# vca.net
KiCad netlist of a schematic drawn in EAGLE
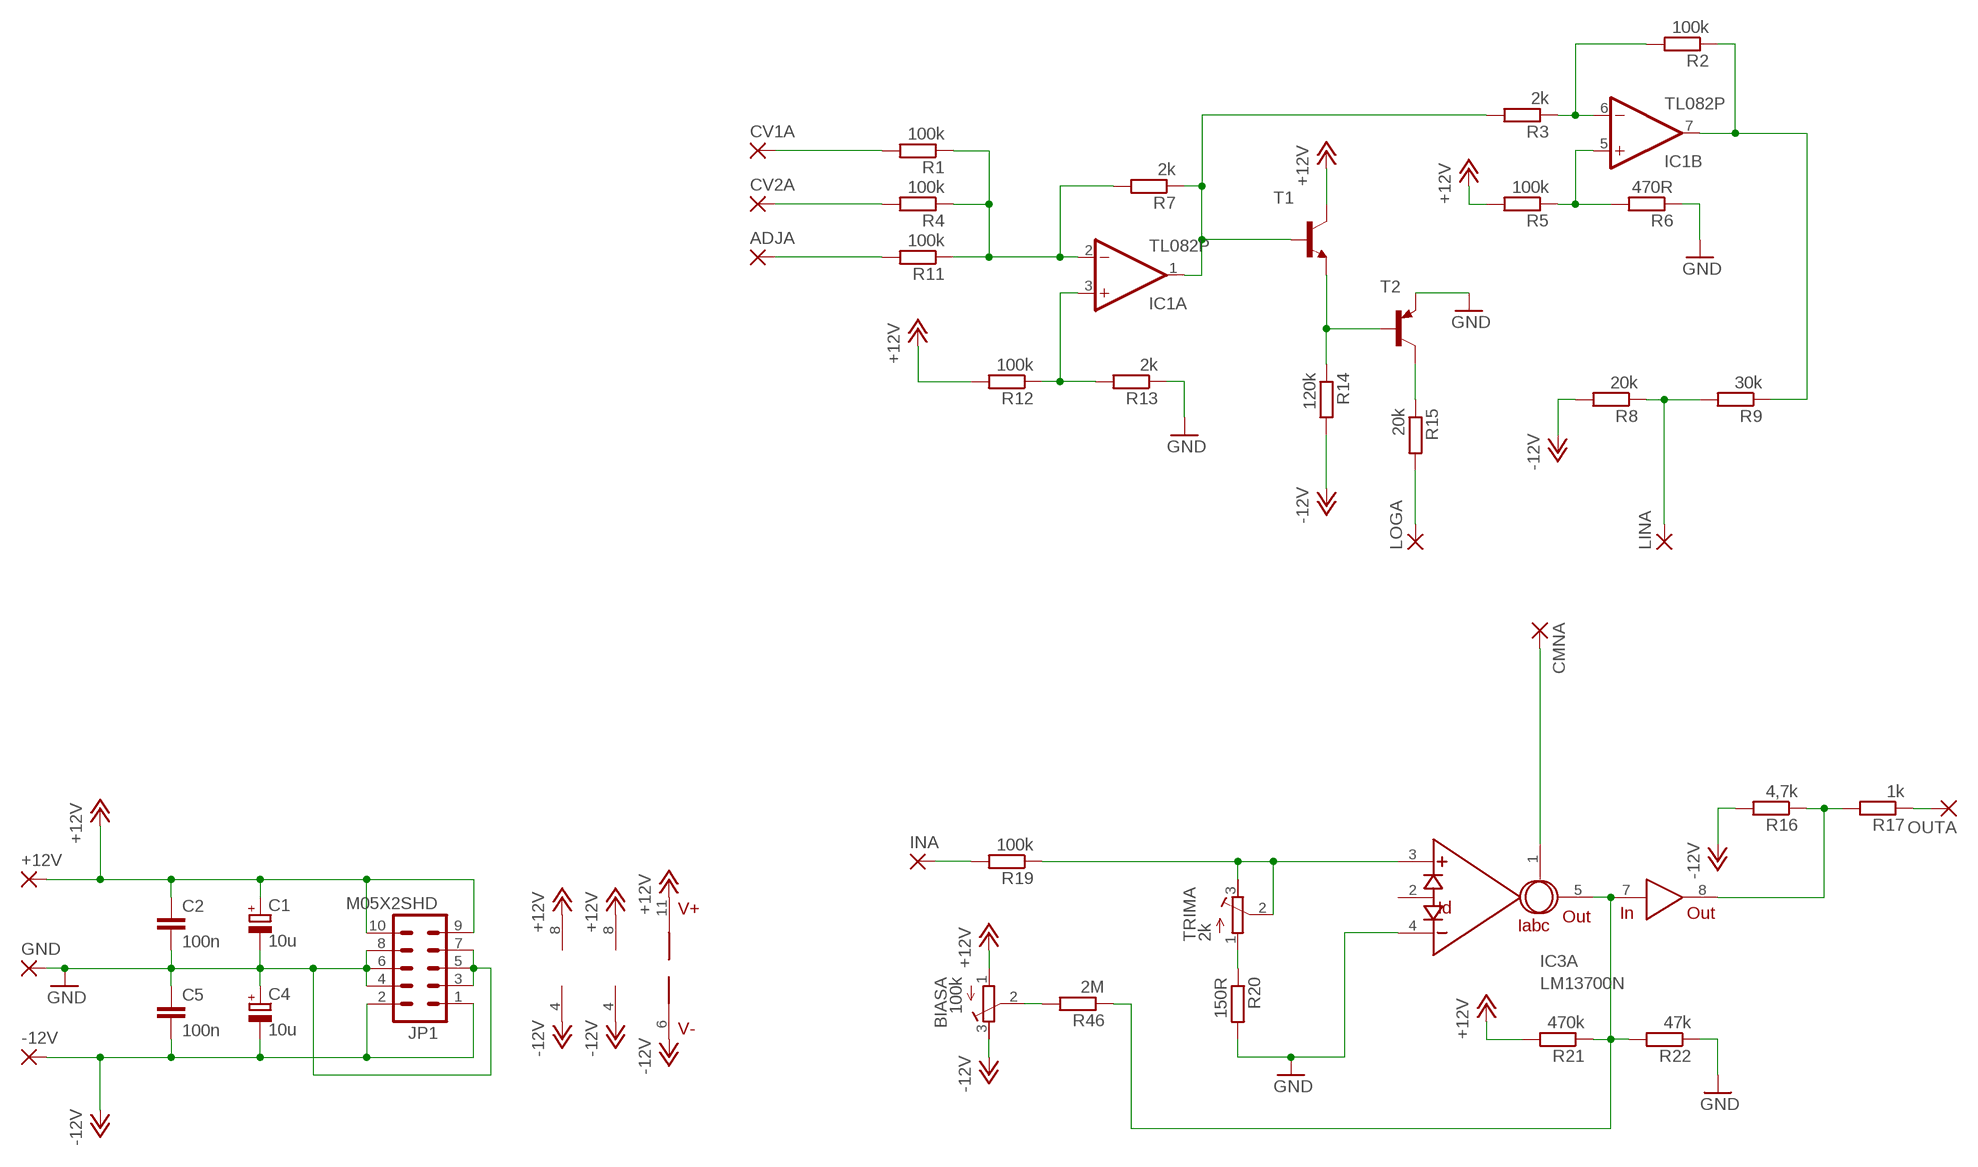
[diagram p0: schematic, sheet 1]
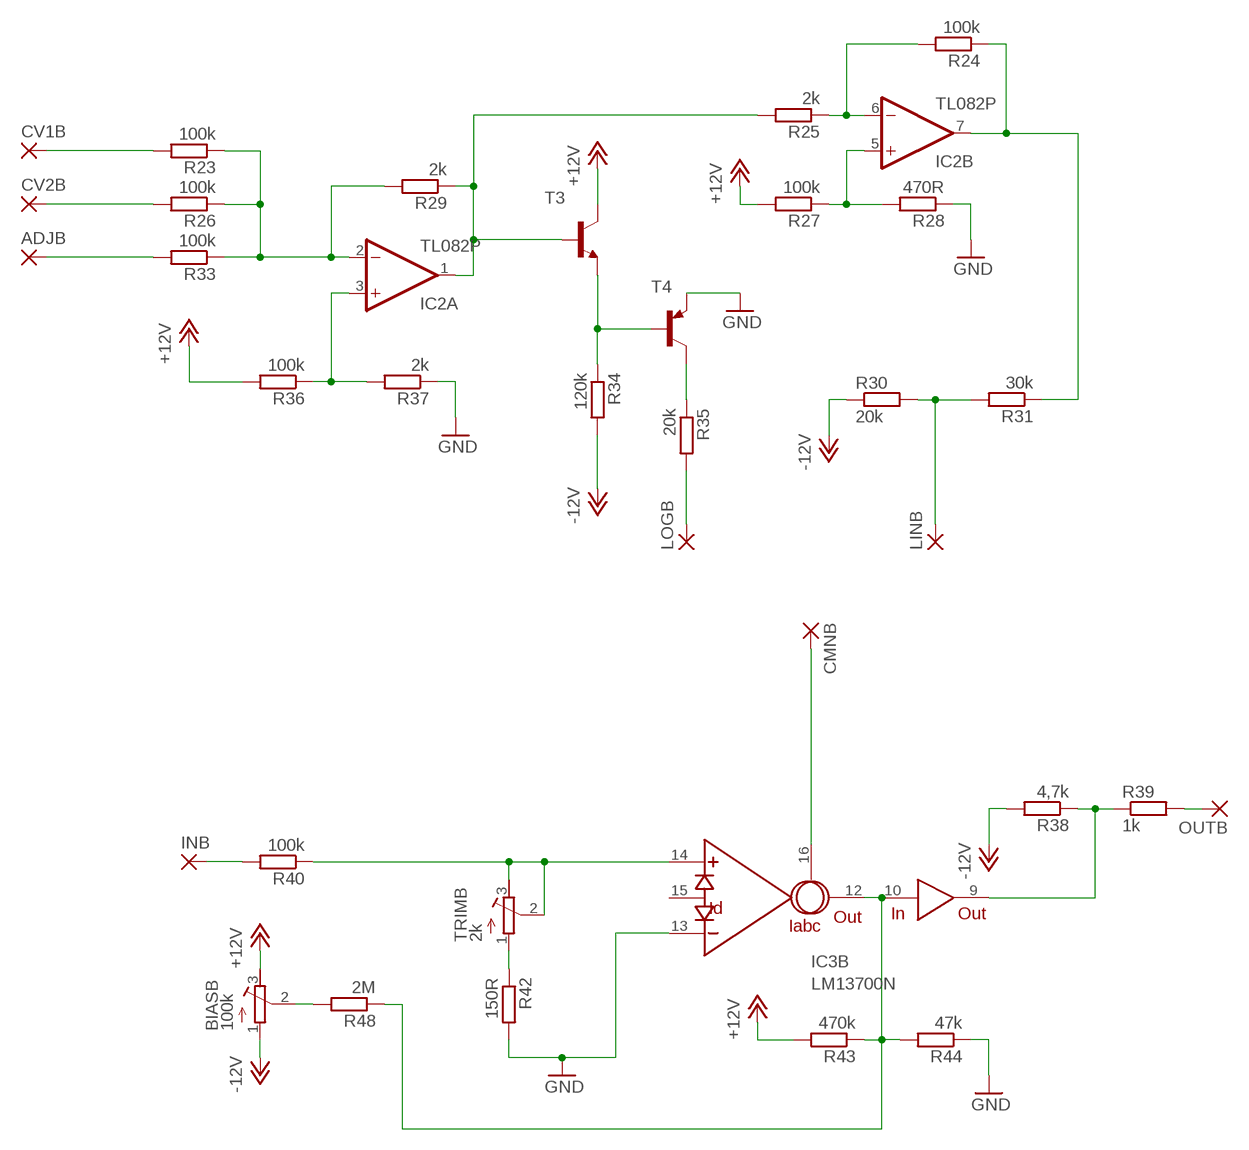
[diagram p1: schematic, sheet 2]

(export (version "E")
  (design (tool "Eeschema 10.0.6"))
  (components
    (comp (ref "ADJB")
      (value "2,54/1,0")
      (footprint "eagle-import:2,54_1,0")
      (libsource (lib "eagle-import") (part "2,54/1,0"))
    )
    (comp (ref "BIASB")
      (value "100k")
      (footprint "eagle-import:RTRIM64W")
      (libsource (lib "eagle-import") (part "R-TRIMM64W"))
    )
    (comp (ref "CMNB")
      (value "2,54/1,0")
      (footprint "eagle-import:2,54_1,0")
      (libsource (lib "eagle-import") (part "2,54/1,0"))
    )
    (comp (ref "CV1B")
      (value "2,54/1,0")
      (footprint "eagle-import:2,54_1,0")
      (libsource (lib "eagle-import") (part "2,54/1,0"))
    )
    (comp (ref "CV2B")
      (value "2,54/1,0")
      (footprint "eagle-import:2,54_1,0")
      (libsource (lib "eagle-import") (part "2,54/1,0"))
    )
    (comp (ref "IC2")
      (value "TL082P")
      (footprint "eagle-import:DIL08")
      (libsource (lib "eagle-import") (part "TL082P"))
    )
    (comp (ref "IC3")
      (value "LM13700N")
      (footprint "eagle-import:DIL16")
      (libsource (lib "eagle-import") (part "LM13700N"))
    )
    (comp (ref "INB")
      (value "2,54/1,0")
      (footprint "eagle-import:2,54_1,0")
      (libsource (lib "eagle-import") (part "2,54/1,0"))
    )
    (comp (ref "LINB")
      (value "2,54/1,0")
      (footprint "eagle-import:2,54_1,0")
      (libsource (lib "eagle-import") (part "2,54/1,0"))
    )
    (comp (ref "LOGB")
      (value "2,54/1,0")
      (footprint "eagle-import:2,54_1,0")
      (libsource (lib "eagle-import") (part "2,54/1,0"))
    )
    (comp (ref "OUTB")
      (value "2,54/1,0")
      (footprint "eagle-import:2,54_1,0")
      (libsource (lib "eagle-import") (part "2,54/1,0"))
    )
    (comp (ref "R23")
      (value "100k")
      (footprint "eagle-import:0309V")
      (libsource (lib "eagle-import") (part "R-EU_0309/V"))
    )
    (comp (ref "R24")
      (value "100k")
      (footprint "eagle-import:0309_10")
      (libsource (lib "eagle-import") (part "R-EU_0309/10"))
    )
    (comp (ref "R25")
      (value "2k")
      (footprint "eagle-import:0309_10")
      (libsource (lib "eagle-import") (part "R-EU_0309/10"))
    )
    (comp (ref "R26")
      (value "100k")
      (footprint "eagle-import:0309V")
      (libsource (lib "eagle-import") (part "R-EU_0309/V"))
    )
    (comp (ref "R27")
      (value "100k")
      (footprint "eagle-import:0309_10")
      (libsource (lib "eagle-import") (part "R-EU_0309/10"))
    )
    (comp (ref "R28")
      (value "470R")
      (footprint "eagle-import:0309_10")
      (libsource (lib "eagle-import") (part "R-EU_0309/10"))
    )
    (comp (ref "R29")
      (value "2k")
      (footprint "eagle-import:0309_10")
      (libsource (lib "eagle-import") (part "R-EU_0309/10"))
    )
    (comp (ref "R30")
      (value "20k")
      (footprint "eagle-import:0309V")
      (libsource (lib "eagle-import") (part "R-EU_0309/V"))
    )
    (comp (ref "R31")
      (value "30k")
      (footprint "eagle-import:0309V")
      (libsource (lib "eagle-import") (part "R-EU_0309/V"))
    )
    (comp (ref "R33")
      (value "100k")
      (footprint "eagle-import:0309V")
      (libsource (lib "eagle-import") (part "R-EU_0309/V"))
    )
    (comp (ref "R34")
      (value "120k")
      (footprint "eagle-import:0309_10")
      (libsource (lib "eagle-import") (part "R-EU_0309/10"))
    )
    (comp (ref "R35")
      (value "20k")
      (footprint "eagle-import:0309_10")
      (libsource (lib "eagle-import") (part "R-EU_0309/10"))
    )
    (comp (ref "R36")
      (value "100k")
      (footprint "eagle-import:0309_10")
      (libsource (lib "eagle-import") (part "R-EU_0309/10"))
    )
    (comp (ref "R37")
      (value "2k")
      (footprint "eagle-import:0309_10")
      (libsource (lib "eagle-import") (part "R-EU_0309/10"))
    )
    (comp (ref "R38")
      (value "4,7k")
      (footprint "eagle-import:0309_10")
      (libsource (lib "eagle-import") (part "R-EU_0309/10"))
    )
    (comp (ref "R39")
      (value "1k")
      (footprint "eagle-import:0309V")
      (libsource (lib "eagle-import") (part "R-EU_0309/V"))
    )
    (comp (ref "R40")
      (value "100k")
      (footprint "eagle-import:0309V")
      (libsource (lib "eagle-import") (part "R-EU_0309/V"))
    )
    (comp (ref "R42")
      (value "150R")
      (footprint "eagle-import:0309_10")
      (libsource (lib "eagle-import") (part "R-EU_0309/10"))
    )
    (comp (ref "R43")
      (value "470k")
      (footprint "eagle-import:0309_10")
      (libsource (lib "eagle-import") (part "R-EU_0309/10"))
    )
    (comp (ref "R44")
      (value "47k")
      (footprint "eagle-import:0309_10")
      (libsource (lib "eagle-import") (part "R-EU_0309/10"))
    )
    (comp (ref "R48")
      (value "2M")
      (footprint "eagle-import:0309_10")
      (libsource (lib "eagle-import") (part "R-EU_0309/10"))
    )
    (comp (ref "T3")
      (value "2N3904-NPN-TO92-EBC")
      (footprint "eagle-import:TO92-EBC")
      (libsource (lib "eagle-import") (part "-NPN-TO92-EBC2N3904"))
    )
    (comp (ref "T4")
      (value "2N3906-PNP-TO92-EBC")
      (footprint "eagle-import:TO92-EBC")
      (libsource (lib "eagle-import") (part "-PNP-TO92-EBC2N3906"))
    )
    (comp (ref "TRIMB")
      (value "2k")
      (footprint "eagle-import:RTRIM64W")
      (libsource (lib "eagle-import") (part "R-TRIMM64W"))
    )
    (comp (ref "+12V")
      (value "2,54/1,0")
      (footprint "eagle-import:2,54_1,0")
      (libsource (lib "eagle-import") (part "2,54/1,0"))
    )
    (comp (ref "-12V")
      (value "2,54/1,0")
      (footprint "eagle-import:2,54_1,0")
      (libsource (lib "eagle-import") (part "2,54/1,0"))
    )
    (comp (ref "ADJA")
      (value "2,54/1,0")
      (footprint "eagle-import:2,54_1,0")
      (libsource (lib "eagle-import") (part "2,54/1,0"))
    )
    (comp (ref "BIASA")
      (value "100k")
      (footprint "eagle-import:RTRIM64W")
      (libsource (lib "eagle-import") (part "R-TRIMM64W"))
    )
    (comp (ref "C1")
      (value "10u")
      (footprint "eagle-import:E3,5-8")
      (libsource (lib "eagle-import") (part "CPOL-EUE3.5-8"))
    )
    (comp (ref "C2")
      (value "100n")
      (footprint "eagle-import:C050-035X075")
      (libsource (lib "eagle-import") (part "C-EU050-035X075"))
    )
    (comp (ref "C4")
      (value "10u")
      (footprint "eagle-import:E3,5-8")
      (libsource (lib "eagle-import") (part "CPOL-EUE3.5-8"))
    )
    (comp (ref "C5")
      (value "100n")
      (footprint "eagle-import:C050-035X075")
      (libsource (lib "eagle-import") (part "C-EU050-035X075"))
    )
    (comp (ref "CMNA")
      (value "2,54/1,0")
      (footprint "eagle-import:2,54_1,0")
      (libsource (lib "eagle-import") (part "2,54/1,0"))
    )
    (comp (ref "CV1A")
      (value "2,54/1,0")
      (footprint "eagle-import:2,54_1,0")
      (libsource (lib "eagle-import") (part "2,54/1,0"))
    )
    (comp (ref "CV2A")
      (value "2,54/1,0")
      (footprint "eagle-import:2,54_1,0")
      (libsource (lib "eagle-import") (part "2,54/1,0"))
    )
    (comp (ref "GND")
      (value "2,54/1,0")
      (footprint "eagle-import:2,54_1,0")
      (libsource (lib "eagle-import") (part "2,54/1,0"))
    )
    (comp (ref "IC1")
      (value "TL082P")
      (footprint "eagle-import:DIL08")
      (libsource (lib "eagle-import") (part "TL082P"))
    )
    (comp (ref "INA")
      (value "2,54/1,0")
      (footprint "eagle-import:2,54_1,0")
      (libsource (lib "eagle-import") (part "2,54/1,0"))
    )
    (comp (ref "JP1")
      (value "M05X2SHD")
      (footprint "eagle-import:2X5-SHROUDED")
      (libsource (lib "eagle-import") (part "M05X2SHD"))
    )
    (comp (ref "LINA")
      (value "2,54/1,0")
      (footprint "eagle-import:2,54_1,0")
      (libsource (lib "eagle-import") (part "2,54/1,0"))
    )
    (comp (ref "LOGA")
      (value "2,54/1,0")
      (footprint "eagle-import:2,54_1,0")
      (libsource (lib "eagle-import") (part "2,54/1,0"))
    )
    (comp (ref "OUTA")
      (value "2,54/1,0")
      (footprint "eagle-import:2,54_1,0")
      (libsource (lib "eagle-import") (part "2,54/1,0"))
    )
    (comp (ref "R1")
      (value "100k")
      (footprint "eagle-import:0309V")
      (libsource (lib "eagle-import") (part "R-EU_0309/V"))
    )
    (comp (ref "R2")
      (value "100k")
      (footprint "eagle-import:0309_10")
      (libsource (lib "eagle-import") (part "R-EU_0309/10"))
    )
    (comp (ref "R3")
      (value "2k")
      (footprint "eagle-import:0309_10")
      (libsource (lib "eagle-import") (part "R-EU_0309/10"))
    )
    (comp (ref "R4")
      (value "100k")
      (footprint "eagle-import:0309V")
      (libsource (lib "eagle-import") (part "R-EU_0309/V"))
    )
    (comp (ref "R5")
      (value "100k")
      (footprint "eagle-import:0309_10")
      (libsource (lib "eagle-import") (part "R-EU_0309/10"))
    )
    (comp (ref "R6")
      (value "470R")
      (footprint "eagle-import:0309_10")
      (libsource (lib "eagle-import") (part "R-EU_0309/10"))
    )
    (comp (ref "R7")
      (value "2k")
      (footprint "eagle-import:0309V")
      (libsource (lib "eagle-import") (part "R-EU_0309/V"))
    )
    (comp (ref "R8")
      (value "20k")
      (footprint "eagle-import:0309_10")
      (libsource (lib "eagle-import") (part "R-EU_0309/10"))
    )
    (comp (ref "R9")
      (value "30k")
      (footprint "eagle-import:0309V")
      (libsource (lib "eagle-import") (part "R-EU_0309/V"))
    )
    (comp (ref "R11")
      (value "100k")
      (footprint "eagle-import:0309V")
      (libsource (lib "eagle-import") (part "R-EU_0309/V"))
    )
    (comp (ref "R12")
      (value "100k")
      (footprint "eagle-import:0309_10")
      (libsource (lib "eagle-import") (part "R-EU_0309/10"))
    )
    (comp (ref "R13")
      (value "2k")
      (footprint "eagle-import:0309_10")
      (libsource (lib "eagle-import") (part "R-EU_0309/10"))
    )
    (comp (ref "R14")
      (value "120k")
      (footprint "eagle-import:0309_10")
      (libsource (lib "eagle-import") (part "R-EU_0309/10"))
    )
    (comp (ref "R15")
      (value "20k")
      (footprint "eagle-import:0309V")
      (libsource (lib "eagle-import") (part "R-EU_0309/V"))
    )
    (comp (ref "R16")
      (value "4,7k")
      (footprint "eagle-import:0309_10")
      (libsource (lib "eagle-import") (part "R-EU_0309/10"))
    )
    (comp (ref "R17")
      (value "1k")
      (footprint "eagle-import:0309_10")
      (libsource (lib "eagle-import") (part "R-EU_0309/10"))
    )
    (comp (ref "R19")
      (value "100k")
      (footprint "eagle-import:0309_10")
      (libsource (lib "eagle-import") (part "R-EU_0309/10"))
    )
    (comp (ref "R20")
      (value "150R")
      (footprint "eagle-import:0309_10")
      (libsource (lib "eagle-import") (part "R-EU_0309/10"))
    )
    (comp (ref "R21")
      (value "470k")
      (footprint "eagle-import:0309_10")
      (libsource (lib "eagle-import") (part "R-EU_0309/10"))
    )
    (comp (ref "R22")
      (value "47k")
      (footprint "eagle-import:0309_10")
      (libsource (lib "eagle-import") (part "R-EU_0309/10"))
    )
    (comp (ref "R46")
      (value "2M")
      (footprint "eagle-import:0309_10")
      (libsource (lib "eagle-import") (part "R-EU_0309/10"))
    )
    (comp (ref "T1")
      (value "2N3904-NPN-TO92-EBC")
      (footprint "eagle-import:TO92-EBC")
      (libsource (lib "eagle-import") (part "-NPN-TO92-EBC2N3904"))
    )
    (comp (ref "T2")
      (value "2N3906-PNP-TO92-EBC")
      (footprint "eagle-import:TO92-EBC")
      (libsource (lib "eagle-import") (part "-PNP-TO92-EBC2N3906"))
    )
    (comp (ref "TRIMA")
      (value "2k")
      (footprint "eagle-import:RTRIM64W")
      (libsource (lib "eagle-import") (part "R-TRIMM64W"))
    )
  )
  (nets
    (net (code "1") (name "+12V") (class "Default")
      (node (ref "+12V") (pin "1") (pinfunction "P_1") (pintype "passive"))
      (node (ref "BIASA") (pin "1") (pinfunction "A_1") (pintype "passive"))
      (node (ref "BIASB") (pin "3") (pinfunction "E_3") (pintype "passive"))
      (node (ref "C1") (pin "+") (pinfunction "+_+") (pintype "passive"))
      (node (ref "C2") (pin "1") (pinfunction "1_1") (pintype "passive"))
      (node (ref "IC1") (pin "8") (pinfunction "V+_8") (pintype "power_in"))
      (node (ref "IC2") (pin "8") (pinfunction "V+_8") (pintype "power_in"))
      (node (ref "IC3") (pin "11") (pinfunction "V+_11") (pintype "bidirectional"))
      (node (ref "JP1") (pin "10") (pinfunction "10_10") (pintype "passive"))
      (node (ref "JP1") (pin "9") (pinfunction "9_9") (pintype "passive"))
      (node (ref "R12") (pin "2") (pinfunction "2_2") (pintype "passive"))
      (node (ref "R21") (pin "2") (pinfunction "2_2") (pintype "passive"))
      (node (ref "R27") (pin "2") (pinfunction "2_2") (pintype "passive"))
      (node (ref "R36") (pin "2") (pinfunction "2_2") (pintype "passive"))
      (node (ref "R43") (pin "2") (pinfunction "2_2") (pintype "passive"))
      (node (ref "R5") (pin "2") (pinfunction "2_2") (pintype "passive"))
      (node (ref "T1") (pin "C") (pinfunction "C_C") (pintype "passive"))
      (node (ref "T3") (pin "C") (pinfunction "C_C") (pintype "passive"))
    )
    (net (code "2") (name "-12V") (class "Default")
      (node (ref "-12V") (pin "1") (pinfunction "P_1") (pintype "passive"))
      (node (ref "BIASA") (pin "3") (pinfunction "E_3") (pintype "passive"))
      (node (ref "BIASB") (pin "1") (pinfunction "A_1") (pintype "passive"))
      (node (ref "C4") (pin "-") (pinfunction "-_-") (pintype "passive"))
      (node (ref "C5") (pin "2") (pinfunction "2_2") (pintype "passive"))
      (node (ref "IC1") (pin "4") (pinfunction "V-_4") (pintype "power_in"))
      (node (ref "IC2") (pin "4") (pinfunction "V-_4") (pintype "power_in"))
      (node (ref "IC3") (pin "6") (pinfunction "V-_6") (pintype "bidirectional"))
      (node (ref "JP1") (pin "1") (pinfunction "1_1") (pintype "passive"))
      (node (ref "JP1") (pin "2") (pinfunction "2_2") (pintype "passive"))
      (node (ref "R14") (pin "2") (pinfunction "2_2") (pintype "passive"))
      (node (ref "R16") (pin "2") (pinfunction "2_2") (pintype "passive"))
      (node (ref "R30") (pin "1") (pinfunction "1_1") (pintype "passive"))
      (node (ref "R34") (pin "2") (pinfunction "2_2") (pintype "passive"))
      (node (ref "R38") (pin "2") (pinfunction "2_2") (pintype "passive"))
      (node (ref "R8") (pin "2") (pinfunction "2_2") (pintype "passive"))
    )
    (net (code "3") (name "GND") (class "Default")
      (node (ref "C1") (pin "-") (pinfunction "-_-") (pintype "passive"))
      (node (ref "C2") (pin "2") (pinfunction "2_2") (pintype "passive"))
      (node (ref "C4") (pin "+") (pinfunction "+_+") (pintype "passive"))
      (node (ref "C5") (pin "1") (pinfunction "1_1") (pintype "passive"))
      (node (ref "GND") (pin "1") (pinfunction "P_1") (pintype "passive"))
      (node (ref "IC3") (pin "13") (pinfunction "-IN_13") (pintype "bidirectional"))
      (node (ref "IC3") (pin "4") (pinfunction "-IN_4") (pintype "bidirectional"))
      (node (ref "JP1") (pin "3") (pinfunction "3_3") (pintype "passive"))
      (node (ref "JP1") (pin "4") (pinfunction "4_4") (pintype "passive"))
      (node (ref "JP1") (pin "5") (pinfunction "5_5") (pintype "passive"))
      (node (ref "JP1") (pin "6") (pinfunction "6_6") (pintype "passive"))
      (node (ref "JP1") (pin "7") (pinfunction "7_7") (pintype "passive"))
      (node (ref "JP1") (pin "8") (pinfunction "8_8") (pintype "passive"))
      (node (ref "R13") (pin "1") (pinfunction "1_1") (pintype "passive"))
      (node (ref "R20") (pin "2") (pinfunction "2_2") (pintype "passive"))
      (node (ref "R22") (pin "1") (pinfunction "1_1") (pintype "passive"))
      (node (ref "R28") (pin "1") (pinfunction "1_1") (pintype "passive"))
      (node (ref "R37") (pin "1") (pinfunction "1_1") (pintype "passive"))
      (node (ref "R42") (pin "2") (pinfunction "2_2") (pintype "passive"))
      (node (ref "R44") (pin "1") (pinfunction "1_1") (pintype "passive"))
      (node (ref "R6") (pin "1") (pinfunction "1_1") (pintype "passive"))
      (node (ref "T2") (pin "E") (pinfunction "E_E") (pintype "passive"))
      (node (ref "T4") (pin "E") (pinfunction "E_E") (pintype "passive"))
    )
    (net (code "4") (name "Net-(ADJA-P)") (class "Default")
      (node (ref "ADJA") (pin "1") (pinfunction "P_1") (pintype "passive"))
      (node (ref "R11") (pin "2") (pinfunction "2_2") (pintype "passive"))
    )
    (net (code "5") (name "Net-(ADJB-P)") (class "Default")
      (node (ref "ADJB") (pin "1") (pinfunction "P_1") (pintype "passive"))
      (node (ref "R33") (pin "2") (pinfunction "2_2") (pintype "passive"))
    )
    (net (code "6") (name "Net-(BIASA-S)") (class "Default")
      (node (ref "BIASA") (pin "2") (pinfunction "S_2") (pintype "passive"))
      (node (ref "R46") (pin "2") (pinfunction "2_2") (pintype "passive"))
    )
    (net (code "7") (name "Net-(BIASB-S)") (class "Default")
      (node (ref "BIASB") (pin "2") (pinfunction "S_2") (pintype "passive"))
      (node (ref "R48") (pin "2") (pinfunction "2_2") (pintype "passive"))
    )
    (net (code "8") (name "Net-(CMNA-P)") (class "Default")
      (node (ref "CMNA") (pin "1") (pinfunction "P_1") (pintype "passive"))
      (node (ref "IC3") (pin "1") (pinfunction "IABC_1") (pintype "bidirectional"))
    )
    (net (code "9") (name "Net-(CMNB-P)") (class "Default")
      (node (ref "CMNB") (pin "1") (pinfunction "P_1") (pintype "passive"))
      (node (ref "IC3") (pin "16") (pinfunction "IABC_16") (pintype "bidirectional"))
    )
    (net (code "10") (name "Net-(CV1A-P)") (class "Default")
      (node (ref "CV1A") (pin "1") (pinfunction "P_1") (pintype "passive"))
      (node (ref "R1") (pin "2") (pinfunction "2_2") (pintype "passive"))
    )
    (net (code "11") (name "Net-(CV1B-P)") (class "Default")
      (node (ref "CV1B") (pin "1") (pinfunction "P_1") (pintype "passive"))
      (node (ref "R23") (pin "2") (pinfunction "2_2") (pintype "passive"))
    )
    (net (code "12") (name "Net-(CV2A-P)") (class "Default")
      (node (ref "CV2A") (pin "1") (pinfunction "P_1") (pintype "passive"))
      (node (ref "R4") (pin "2") (pinfunction "2_2") (pintype "passive"))
    )
    (net (code "13") (name "Net-(CV2B-P)") (class "Default")
      (node (ref "CV2B") (pin "1") (pinfunction "P_1") (pintype "passive"))
      (node (ref "R26") (pin "2") (pinfunction "2_2") (pintype "passive"))
    )
    (net (code "14") (name "Net-(IC1A-+IN)") (class "Default")
      (node (ref "IC1") (pin "3") (pinfunction "+IN_3") (pintype "input"))
      (node (ref "R12") (pin "1") (pinfunction "1_1") (pintype "passive"))
      (node (ref "R13") (pin "2") (pinfunction "2_2") (pintype "passive"))
    )
    (net (code "15") (name "Net-(IC1A--IN)") (class "Default")
      (node (ref "IC1") (pin "2") (pinfunction "-IN_2") (pintype "input"))
      (node (ref "R1") (pin "1") (pinfunction "1_1") (pintype "passive"))
      (node (ref "R11") (pin "1") (pinfunction "1_1") (pintype "passive"))
      (node (ref "R4") (pin "1") (pinfunction "1_1") (pintype "passive"))
      (node (ref "R7") (pin "2") (pinfunction "2_2") (pintype "passive"))
    )
    (net (code "16") (name "Net-(IC1A-OUT)") (class "Default")
      (node (ref "IC1") (pin "1") (pinfunction "OUT_1") (pintype "output"))
      (node (ref "R3") (pin "2") (pinfunction "2_2") (pintype "passive"))
      (node (ref "R7") (pin "1") (pinfunction "1_1") (pintype "passive"))
      (node (ref "T1") (pin "B") (pinfunction "B_B") (pintype "passive"))
    )
    (net (code "17") (name "Net-(IC1B-+IN)") (class "Default")
      (node (ref "IC1") (pin "5") (pinfunction "+IN_5") (pintype "input"))
      (node (ref "R5") (pin "1") (pinfunction "1_1") (pintype "passive"))
      (node (ref "R6") (pin "2") (pinfunction "2_2") (pintype "passive"))
    )
    (net (code "18") (name "Net-(IC1B--IN)") (class "Default")
      (node (ref "IC1") (pin "6") (pinfunction "-IN_6") (pintype "input"))
      (node (ref "R2") (pin "2") (pinfunction "2_2") (pintype "passive"))
      (node (ref "R3") (pin "1") (pinfunction "1_1") (pintype "passive"))
    )
    (net (code "19") (name "Net-(IC1B-OUT)") (class "Default")
      (node (ref "IC1") (pin "7") (pinfunction "OUT_7") (pintype "output"))
      (node (ref "R2") (pin "1") (pinfunction "1_1") (pintype "passive"))
      (node (ref "R9") (pin "1") (pinfunction "1_1") (pintype "passive"))
    )
    (net (code "20") (name "Net-(IC2A-+IN)") (class "Default")
      (node (ref "IC2") (pin "3") (pinfunction "+IN_3") (pintype "input"))
      (node (ref "R36") (pin "1") (pinfunction "1_1") (pintype "passive"))
      (node (ref "R37") (pin "2") (pinfunction "2_2") (pintype "passive"))
    )
    (net (code "21") (name "Net-(IC2A--IN)") (class "Default")
      (node (ref "IC2") (pin "2") (pinfunction "-IN_2") (pintype "input"))
      (node (ref "R23") (pin "1") (pinfunction "1_1") (pintype "passive"))
      (node (ref "R26") (pin "1") (pinfunction "1_1") (pintype "passive"))
      (node (ref "R29") (pin "2") (pinfunction "2_2") (pintype "passive"))
      (node (ref "R33") (pin "1") (pinfunction "1_1") (pintype "passive"))
    )
    (net (code "22") (name "Net-(IC2A-OUT)") (class "Default")
      (node (ref "IC2") (pin "1") (pinfunction "OUT_1") (pintype "output"))
      (node (ref "R25") (pin "2") (pinfunction "2_2") (pintype "passive"))
      (node (ref "R29") (pin "1") (pinfunction "1_1") (pintype "passive"))
      (node (ref "T3") (pin "B") (pinfunction "B_B") (pintype "passive"))
    )
    (net (code "23") (name "Net-(IC2B-+IN)") (class "Default")
      (node (ref "IC2") (pin "5") (pinfunction "+IN_5") (pintype "input"))
      (node (ref "R27") (pin "1") (pinfunction "1_1") (pintype "passive"))
      (node (ref "R28") (pin "2") (pinfunction "2_2") (pintype "passive"))
    )
    (net (code "24") (name "Net-(IC2B--IN)") (class "Default")
      (node (ref "IC2") (pin "6") (pinfunction "-IN_6") (pintype "input"))
      (node (ref "R24") (pin "2") (pinfunction "2_2") (pintype "passive"))
      (node (ref "R25") (pin "1") (pinfunction "1_1") (pintype "passive"))
    )
    (net (code "25") (name "Net-(IC2B-OUT)") (class "Default")
      (node (ref "IC2") (pin "7") (pinfunction "OUT_7") (pintype "output"))
      (node (ref "R24") (pin "1") (pinfunction "1_1") (pintype "passive"))
      (node (ref "R31") (pin "1") (pinfunction "1_1") (pintype "passive"))
    )
    (net (code "26") (name "Net-(IC3A-+IN)") (class "Default")
      (node (ref "IC3") (pin "3") (pinfunction "+IN_3") (pintype "bidirectional"))
      (node (ref "R19") (pin "1") (pinfunction "1_1") (pintype "passive"))
      (node (ref "TRIMA") (pin "2") (pinfunction "S_2") (pintype "passive"))
      (node (ref "TRIMA") (pin "3") (pinfunction "E_3") (pintype "passive"))
    )
    (net (code "27") (name "Net-(IC3A-OUT)") (class "Default")
      (node (ref "IC3") (pin "5") (pinfunction "OUT_5") (pintype "bidirectional"))
      (node (ref "IC3") (pin "7") (pinfunction "IN_7") (pintype "bidirectional"))
      (node (ref "R21") (pin "1") (pinfunction "1_1") (pintype "passive"))
      (node (ref "R22") (pin "2") (pinfunction "2_2") (pintype "passive"))
      (node (ref "R46") (pin "1") (pinfunction "1_1") (pintype "passive"))
    )
    (net (code "28") (name "Net-(IC3B-+IN)") (class "Default")
      (node (ref "IC3") (pin "14") (pinfunction "+IN_14") (pintype "bidirectional"))
      (node (ref "R40") (pin "1") (pinfunction "1_1") (pintype "passive"))
      (node (ref "TRIMB") (pin "2") (pinfunction "S_2") (pintype "passive"))
      (node (ref "TRIMB") (pin "3") (pinfunction "E_3") (pintype "passive"))
    )
    (net (code "29") (name "Net-(IC3B-OUT)") (class "Default")
      (node (ref "IC3") (pin "10") (pinfunction "IN_10") (pintype "bidirectional"))
      (node (ref "IC3") (pin "12") (pinfunction "OUT_12") (pintype "bidirectional"))
      (node (ref "R43") (pin "1") (pinfunction "1_1") (pintype "passive"))
      (node (ref "R44") (pin "2") (pinfunction "2_2") (pintype "passive"))
      (node (ref "R48") (pin "1") (pinfunction "1_1") (pintype "passive"))
    )
    (net (code "30") (name "Net-(IC3C-OUT)") (class "Default")
      (node (ref "IC3") (pin "8") (pinfunction "OUT_8") (pintype "bidirectional"))
      (node (ref "R16") (pin "1") (pinfunction "1_1") (pintype "passive"))
      (node (ref "R17") (pin "2") (pinfunction "2_2") (pintype "passive"))
    )
    (net (code "31") (name "Net-(IC3D-OUT)") (class "Default")
      (node (ref "IC3") (pin "9") (pinfunction "OUT_9") (pintype "bidirectional"))
      (node (ref "R38") (pin "1") (pinfunction "1_1") (pintype "passive"))
      (node (ref "R39") (pin "1") (pinfunction "1_1") (pintype "passive"))
    )
    (net (code "32") (name "Net-(INA-P)") (class "Default")
      (node (ref "INA") (pin "1") (pinfunction "P_1") (pintype "passive"))
      (node (ref "R19") (pin "2") (pinfunction "2_2") (pintype "passive"))
    )
    (net (code "33") (name "Net-(INB-P)") (class "Default")
      (node (ref "INB") (pin "1") (pinfunction "P_1") (pintype "passive"))
      (node (ref "R40") (pin "2") (pinfunction "2_2") (pintype "passive"))
    )
    (net (code "34") (name "Net-(LINA-P)") (class "Default")
      (node (ref "LINA") (pin "1") (pinfunction "P_1") (pintype "passive"))
      (node (ref "R8") (pin "1") (pinfunction "1_1") (pintype "passive"))
      (node (ref "R9") (pin "2") (pinfunction "2_2") (pintype "passive"))
    )
    (net (code "35") (name "Net-(LINB-P)") (class "Default")
      (node (ref "LINB") (pin "1") (pinfunction "P_1") (pintype "passive"))
      (node (ref "R30") (pin "2") (pinfunction "2_2") (pintype "passive"))
      (node (ref "R31") (pin "2") (pinfunction "2_2") (pintype "passive"))
    )
    (net (code "36") (name "Net-(LOGA-P)") (class "Default")
      (node (ref "LOGA") (pin "1") (pinfunction "P_1") (pintype "passive"))
      (node (ref "R15") (pin "2") (pinfunction "2_2") (pintype "passive"))
    )
    (net (code "37") (name "Net-(LOGB-P)") (class "Default")
      (node (ref "LOGB") (pin "1") (pinfunction "P_1") (pintype "passive"))
      (node (ref "R35") (pin "2") (pinfunction "2_2") (pintype "passive"))
    )
    (net (code "38") (name "Net-(OUTA-P)") (class "Default")
      (node (ref "OUTA") (pin "1") (pinfunction "P_1") (pintype "passive"))
      (node (ref "R17") (pin "1") (pinfunction "1_1") (pintype "passive"))
    )
    (net (code "39") (name "Net-(OUTB-P)") (class "Default")
      (node (ref "OUTB") (pin "1") (pinfunction "P_1") (pintype "passive"))
      (node (ref "R39") (pin "2") (pinfunction "2_2") (pintype "passive"))
    )
    (net (code "40") (name "Net-(R14-Pad1)") (class "Default")
      (node (ref "R14") (pin "1") (pinfunction "1_1") (pintype "passive"))
      (node (ref "T1") (pin "E") (pinfunction "E_E") (pintype "passive"))
      (node (ref "T2") (pin "B") (pinfunction "B_B") (pintype "passive"))
    )
    (net (code "41") (name "Net-(R15-Pad1)") (class "Default")
      (node (ref "R15") (pin "1") (pinfunction "1_1") (pintype "passive"))
      (node (ref "T2") (pin "C") (pinfunction "C_C") (pintype "passive"))
    )
    (net (code "42") (name "Net-(R34-Pad1)") (class "Default")
      (node (ref "R34") (pin "1") (pinfunction "1_1") (pintype "passive"))
      (node (ref "T3") (pin "E") (pinfunction "E_E") (pintype "passive"))
      (node (ref "T4") (pin "B") (pinfunction "B_B") (pintype "passive"))
    )
    (net (code "43") (name "Net-(R35-Pad1)") (class "Default")
      (node (ref "R35") (pin "1") (pinfunction "1_1") (pintype "passive"))
      (node (ref "T4") (pin "C") (pinfunction "C_C") (pintype "passive"))
    )
    (net (code "44") (name "Net-(TRIMA-A)") (class "Default")
      (node (ref "R20") (pin "1") (pinfunction "1_1") (pintype "passive"))
      (node (ref "TRIMA") (pin "1") (pinfunction "A_1") (pintype "passive"))
    )
    (net (code "45") (name "Net-(TRIMB-A)") (class "Default")
      (node (ref "R42") (pin "1") (pinfunction "1_1") (pintype "passive"))
      (node (ref "TRIMB") (pin "1") (pinfunction "A_1") (pintype "passive"))
    )
    (net (code "46") (name "unconnected-(IC3A-ID-Pad2)") (class "Default")
      (node (ref "IC3") (pin "2") (pinfunction "ID_2") (pintype "bidirectional"))
    )
    (net (code "47") (name "unconnected-(IC3B-ID-Pad15)") (class "Default")
      (node (ref "IC3") (pin "15") (pinfunction "ID_15") (pintype "bidirectional"))
    )
  )
)
